# MotorControl.net
KiCad netlist of a schematic drawn in Altium Designer
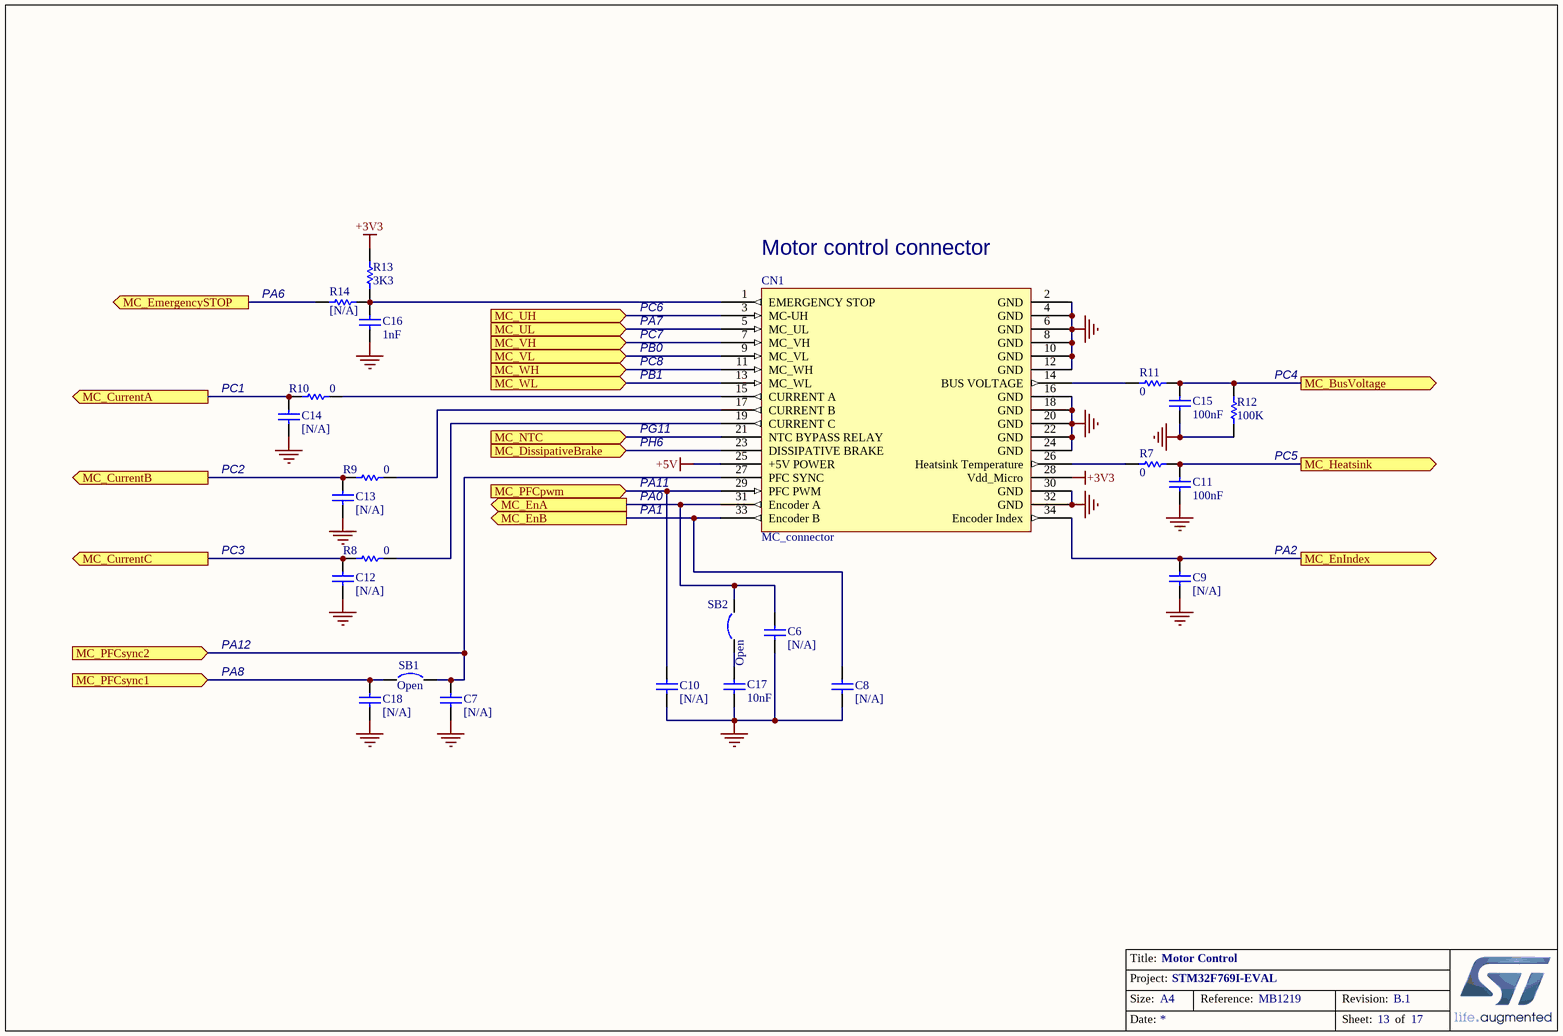
[diagram p0: MotorControl.SchDoc]

(export (version "E")
  (design (tool "Eeschema 10.0.6"))
  (components
    (comp (ref "C6")
      (value "[N/A]")
      (footprint "0603C")
      (description "Capacitor")
      (fields (field (name "PUBLISHER") "Altium Limited"))
      (libsource (lib "Miscellaneous Devices") (part "cap"))
    )
    (comp (ref "C7")
      (value "[N/A]")
      (footprint "0603C")
      (description "Capacitor")
      (fields (field (name "PUBLISHER") "Altium Limited"))
      (libsource (lib "Miscellaneous Devices") (part "cap"))
    )
    (comp (ref "C8")
      (value "[N/A]")
      (footprint "0603C")
      (description "Capacitor")
      (fields (field (name "PUBLISHER") "Altium Limited"))
      (libsource (lib "Miscellaneous Devices") (part "cap"))
    )
    (comp (ref "C9")
      (value "[N/A]")
      (footprint "0603C")
      (description "Capacitor")
      (fields (field (name "PUBLISHER") "Altium Limited"))
      (libsource (lib "Miscellaneous Devices") (part "cap"))
    )
    (comp (ref "C10")
      (value "[N/A]")
      (footprint "0603C")
      (description "Capacitor")
      (fields (field (name "PUBLISHER") "Altium Limited"))
      (libsource (lib "Miscellaneous Devices") (part "cap"))
    )
    (comp (ref "C11")
      (value "100nF")
      (footprint "0603C")
      (description "Capacitor")
      (fields (field (name "PUBLISHER") "Altium Limited"))
      (libsource (lib "Miscellaneous Devices") (part "Cap"))
    )
    (comp (ref "C12")
      (value "[N/A]")
      (footprint "0603C")
      (description "Capacitor")
      (fields (field (name "PUBLISHER") "Altium Limited"))
      (libsource (lib "Miscellaneous Devices") (part "cap"))
    )
    (comp (ref "C13")
      (value "[N/A]")
      (footprint "0603C")
      (description "Capacitor")
      (fields (field (name "PUBLISHER") "Altium Limited"))
      (libsource (lib "Miscellaneous Devices") (part "cap"))
    )
    (comp (ref "C14")
      (value "[N/A]")
      (footprint "0603C")
      (description "Capacitor")
      (fields (field (name "PUBLISHER") "Altium Limited"))
      (libsource (lib "Miscellaneous Devices") (part "cap"))
    )
    (comp (ref "C15")
      (value "100nF")
      (footprint "0603C")
      (description "Capacitor")
      (fields (field (name "PUBLISHER") "Altium Limited"))
      (libsource (lib "Miscellaneous Devices") (part "Cap"))
    )
    (comp (ref "C16")
      (value "1nF")
      (footprint "0603C")
      (description "Capacitor")
      (fields (field (name "PUBLISHER") "Altium Limited"))
      (libsource (lib "Miscellaneous Devices") (part "CAP"))
    )
    (comp (ref "C17")
      (value "10nF")
      (footprint "0603C")
      (description "Capacitor")
      (fields (field (name "PUBLISHER") "Altium Limited"))
      (libsource (lib "Miscellaneous Devices") (part "CAP"))
    )
    (comp (ref "C18")
      (value "[N/A]")
      (footprint "0603C")
      (description "Capacitor")
      (fields (field (name "PUBLISHER") "Altium Limited"))
      (libsource (lib "Miscellaneous Devices") (part "cap"))
    )
    (comp (ref "CN1")
      (value "MC_connector")
      (footprint "IDC34S")
      (libsource (lib "MB525") (part "MC_connector"))
    )
    (comp (ref "R7")
      (value "0")
      (footprint "0603R")
      (description "Resistor")
      (fields (field (name "PUBLISHER") "Altium Limited"))
      (libsource (lib "Miscellaneous Devices") (part "Res1"))
    )
    (comp (ref "R8")
      (value "0")
      (footprint "0603R")
      (description "Resistor")
      (fields (field (name "PUBLISHER") "Altium Limited"))
      (libsource (lib "Miscellaneous Devices") (part "Res1"))
    )
    (comp (ref "R9")
      (value "0")
      (footprint "0603R")
      (description "Resistor")
      (fields (field (name "PUBLISHER") "Altium Limited"))
      (libsource (lib "Miscellaneous Devices") (part "Res1"))
    )
    (comp (ref "R10")
      (value "0")
      (footprint "0603R")
      (description "Resistor")
      (fields (field (name "PUBLISHER") "Altium Limited"))
      (libsource (lib "Miscellaneous Devices") (part "Res1"))
    )
    (comp (ref "R11")
      (value "0")
      (footprint "0603R")
      (description "Resistor")
      (fields (field (name "PUBLISHER") "Altium Limited"))
      (libsource (lib "Miscellaneous Devices") (part "Res1"))
    )
    (comp (ref "R12")
      (value "100K")
      (footprint "0603R")
      (description "Resistor")
      (fields (field (name "PUBLISHER") "Altium Limited"))
      (libsource (lib "Miscellaneous Devices") (part "res1"))
    )
    (comp (ref "R13")
      (value "3K3")
      (footprint "0603R")
      (description "Resistor")
      (fields (field (name "PUBLISHER") "Altium Limited"))
      (libsource (lib "Miscellaneous Devices") (part "Res1"))
    )
    (comp (ref "R14")
      (value "[N/A]")
      (footprint "0603R")
      (description "Resistor")
      (fields (field (name "PUBLISHER") "Altium Limited"))
      (libsource (lib "Miscellaneous Devices") (part "Res1"))
    )
    (comp (ref "SB1")
      (value "Open")
      (footprint "SB_0603")
      (description "Circuit Breaker")
      (fields (field (name "PUBLISHER") "Altium Limited"))
      (libsource (lib "MB1167") (part "Circuit Breaker"))
    )
    (comp (ref "SB2")
      (value "Open")
      (footprint "SB_0603")
      (description "Circuit Breaker")
      (fields (field (name "PUBLISHER") "Altium Limited"))
      (libsource (lib "MB1167") (part "Circuit Breaker"))
    )
  )
  (nets
    (net (code "1") (name "+3V3") (class "Default")
      (node (ref "CN1") (pin "28") (pinfunction "Vdd_Micro_28") (pintype "power_in"))
      (node (ref "R13") (pin "2") (pinfunction "2_2") (pintype "passive"))
    )
    (net (code "2") (name "+5V") (class "Default")
      (node (ref "CN1") (pin "25") (pinfunction "+5V_POWER_25") (pintype "power_in"))
    )
    (net (code "3") (name "/MC_BusVoltage") (class "Default")
      (node (ref "C15") (pin "1") (pinfunction "1_1") (pintype "passive"))
      (node (ref "R11") (pin "2") (pinfunction "2_2") (pintype "passive"))
      (node (ref "R12") (pin "1") (pinfunction "1_1") (pintype "passive"))
    )
    (net (code "4") (name "/MC_CurrentA") (class "Default")
      (node (ref "C14") (pin "2") (pinfunction "2_2") (pintype "passive"))
      (node (ref "R10") (pin "1") (pinfunction "1_1") (pintype "passive"))
    )
    (net (code "5") (name "/MC_CurrentB") (class "Default")
      (node (ref "C13") (pin "2") (pinfunction "2_2") (pintype "passive"))
      (node (ref "R9") (pin "1") (pinfunction "1_1") (pintype "passive"))
    )
    (net (code "6") (name "/MC_CurrentC") (class "Default")
      (node (ref "C12") (pin "2") (pinfunction "2_2") (pintype "passive"))
      (node (ref "R8") (pin "1") (pinfunction "1_1") (pintype "passive"))
    )
    (net (code "7") (name "/MC_DissipativeBrake") (class "Default")
      (node (ref "CN1") (pin "23") (pinfunction "DISSIPATIVE_BRAKE_23") (pintype "passive"))
    )
    (net (code "8") (name "/MC_EmergencySTOP") (class "Default")
      (node (ref "R14") (pin "2") (pinfunction "2_2") (pintype "passive"))
    )
    (net (code "9") (name "/MC_EnA") (class "Default")
      (node (ref "C6") (pin "2") (pinfunction "2_2") (pintype "passive"))
      (node (ref "CN1") (pin "31") (pinfunction "Encoder_A_31") (pintype "output"))
      (node (ref "SB2") (pin "2") (pinfunction "2_2") (pintype "passive"))
    )
    (net (code "10") (name "/MC_EnB") (class "Default")
      (node (ref "C8") (pin "2") (pinfunction "2_2") (pintype "passive"))
      (node (ref "CN1") (pin "33") (pinfunction "Encoder_B_33") (pintype "output"))
    )
    (net (code "11") (name "/MC_EnIndex") (class "Default")
      (node (ref "C9") (pin "2") (pinfunction "2_2") (pintype "passive"))
      (node (ref "CN1") (pin "34") (pinfunction "Encoder_Index_34") (pintype "output"))
    )
    (net (code "12") (name "/MC_Heatsink") (class "Default")
      (node (ref "C11") (pin "1") (pinfunction "1_1") (pintype "passive"))
      (node (ref "R7") (pin "2") (pinfunction "2_2") (pintype "passive"))
    )
    (net (code "13") (name "/MC_NTC") (class "Default")
      (node (ref "CN1") (pin "21") (pinfunction "NTC_BYPASS_RELAY_21") (pintype "passive"))
    )
    (net (code "14") (name "/MC_PFCpwm") (class "Default")
      (node (ref "C10") (pin "2") (pinfunction "2_2") (pintype "passive"))
      (node (ref "CN1") (pin "29") (pinfunction "PFC_PWM_29") (pintype "input"))
    )
    (net (code "15") (name "/MC_PFCsync1") (class "Default")
      (node (ref "C18") (pin "2") (pinfunction "2_2") (pintype "passive"))
      (node (ref "SB1") (pin "1") (pinfunction "1_1") (pintype "passive"))
    )
    (net (code "16") (name "/MC_PFCsync2") (class "Default")
      (node (ref "C7") (pin "2") (pinfunction "2_2") (pintype "passive"))
      (node (ref "CN1") (pin "27") (pinfunction "PFC_SYNC_27") (pintype "passive"))
      (node (ref "SB1") (pin "2") (pinfunction "2_2") (pintype "passive"))
    )
    (net (code "17") (name "/MC_UH") (class "Default")
      (node (ref "CN1") (pin "3") (pinfunction "MC-UH_3") (pintype "input"))
    )
    (net (code "18") (name "/MC_UL") (class "Default")
      (node (ref "CN1") (pin "5") (pinfunction "MC_UL_5") (pintype "input"))
    )
    (net (code "19") (name "/MC_VH") (class "Default")
      (node (ref "CN1") (pin "7") (pinfunction "MC_VH_7") (pintype "input"))
    )
    (net (code "20") (name "/MC_VL") (class "Default")
      (node (ref "CN1") (pin "9") (pinfunction "MC_VL_9") (pintype "input"))
    )
    (net (code "21") (name "/MC_WH") (class "Default")
      (node (ref "CN1") (pin "11") (pinfunction "MC_WH_11") (pintype "input"))
    )
    (net (code "22") (name "/MC_WL") (class "Default")
      (node (ref "CN1") (pin "13") (pinfunction "MC_WL_13") (pintype "input"))
    )
    (net (code "23") (name "GND") (class "Default")
      (node (ref "C10") (pin "1") (pinfunction "1_1") (pintype "passive"))
      (node (ref "C11") (pin "2") (pinfunction "2_2") (pintype "passive"))
      (node (ref "C12") (pin "1") (pinfunction "1_1") (pintype "passive"))
      (node (ref "C13") (pin "1") (pinfunction "1_1") (pintype "passive"))
      (node (ref "C14") (pin "1") (pinfunction "1_1") (pintype "passive"))
      (node (ref "C15") (pin "2") (pinfunction "2_2") (pintype "passive"))
      (node (ref "C16") (pin "1") (pinfunction "1_1") (pintype "passive"))
      (node (ref "C17") (pin "2") (pinfunction "2_2") (pintype "passive"))
      (node (ref "C18") (pin "1") (pinfunction "1_1") (pintype "passive"))
      (node (ref "C6") (pin "1") (pinfunction "1_1") (pintype "passive"))
      (node (ref "C7") (pin "1") (pinfunction "1_1") (pintype "passive"))
      (node (ref "C8") (pin "1") (pinfunction "1_1") (pintype "passive"))
      (node (ref "C9") (pin "1") (pinfunction "1_1") (pintype "passive"))
      (node (ref "CN1") (pin "10") (pinfunction "GND_10") (pintype "power_in"))
      (node (ref "CN1") (pin "12") (pinfunction "GND_12") (pintype "power_in"))
      (node (ref "CN1") (pin "16") (pinfunction "GND_16") (pintype "power_in"))
      (node (ref "CN1") (pin "18") (pinfunction "GND_18") (pintype "power_in"))
      (node (ref "CN1") (pin "2") (pinfunction "GND_2") (pintype "power_in"))
      (node (ref "CN1") (pin "20") (pinfunction "GND_20") (pintype "power_in"))
      (node (ref "CN1") (pin "22") (pinfunction "GND_22") (pintype "power_in"))
      (node (ref "CN1") (pin "24") (pinfunction "GND_24") (pintype "power_in"))
      (node (ref "CN1") (pin "30") (pinfunction "GND_30") (pintype "power_in"))
      (node (ref "CN1") (pin "32") (pinfunction "GND_32") (pintype "power_in"))
      (node (ref "CN1") (pin "4") (pinfunction "GND_4") (pintype "power_in"))
      (node (ref "CN1") (pin "6") (pinfunction "GND_6") (pintype "power_in"))
      (node (ref "CN1") (pin "8") (pinfunction "GND_8") (pintype "power_in"))
      (node (ref "R12") (pin "2") (pinfunction "2_2") (pintype "passive"))
    )
    (net (code "24") (name "Net-(C17-Pad1)") (class "Default")
      (node (ref "C17") (pin "1") (pinfunction "1_1") (pintype "passive"))
      (node (ref "SB2") (pin "1") (pinfunction "1_1") (pintype "passive"))
    )
    (net (code "25") (name "Net-(CN1-BUS_VOLTAGE)") (class "Default")
      (node (ref "CN1") (pin "14") (pinfunction "BUS_VOLTAGE_14") (pintype "output"))
      (node (ref "R11") (pin "1") (pinfunction "1_1") (pintype "passive"))
    )
    (net (code "26") (name "Net-(CN1-CURRENT_A)") (class "Default")
      (node (ref "CN1") (pin "15") (pinfunction "CURRENT_A_15") (pintype "output"))
      (node (ref "R10") (pin "2") (pinfunction "2_2") (pintype "passive"))
    )
    (net (code "27") (name "Net-(CN1-CURRENT_B)") (class "Default")
      (node (ref "CN1") (pin "17") (pinfunction "CURRENT_B_17") (pintype "output"))
      (node (ref "R9") (pin "2") (pinfunction "2_2") (pintype "passive"))
    )
    (net (code "28") (name "Net-(CN1-CURRENT_C)") (class "Default")
      (node (ref "CN1") (pin "19") (pinfunction "CURRENT_C_19") (pintype "output"))
      (node (ref "R8") (pin "2") (pinfunction "2_2") (pintype "passive"))
    )
    (net (code "29") (name "Net-(CN1-EMERGENCY_STOP)") (class "Default")
      (node (ref "C16") (pin "2") (pinfunction "2_2") (pintype "passive"))
      (node (ref "CN1") (pin "1") (pinfunction "EMERGENCY_STOP_1") (pintype "output"))
      (node (ref "R13") (pin "1") (pinfunction "1_1") (pintype "passive"))
      (node (ref "R14") (pin "1") (pinfunction "1_1") (pintype "passive"))
    )
    (net (code "30") (name "Net-(CN1-Heatsink_Temperature)") (class "Default")
      (node (ref "CN1") (pin "26") (pinfunction "Heatsink_Temperature_26") (pintype "output"))
      (node (ref "R7") (pin "1") (pinfunction "1_1") (pintype "passive"))
    )
  )
)
